# ASP_LEDBoard.net
KiCad netlist of a schematic drawn in Altium Designer
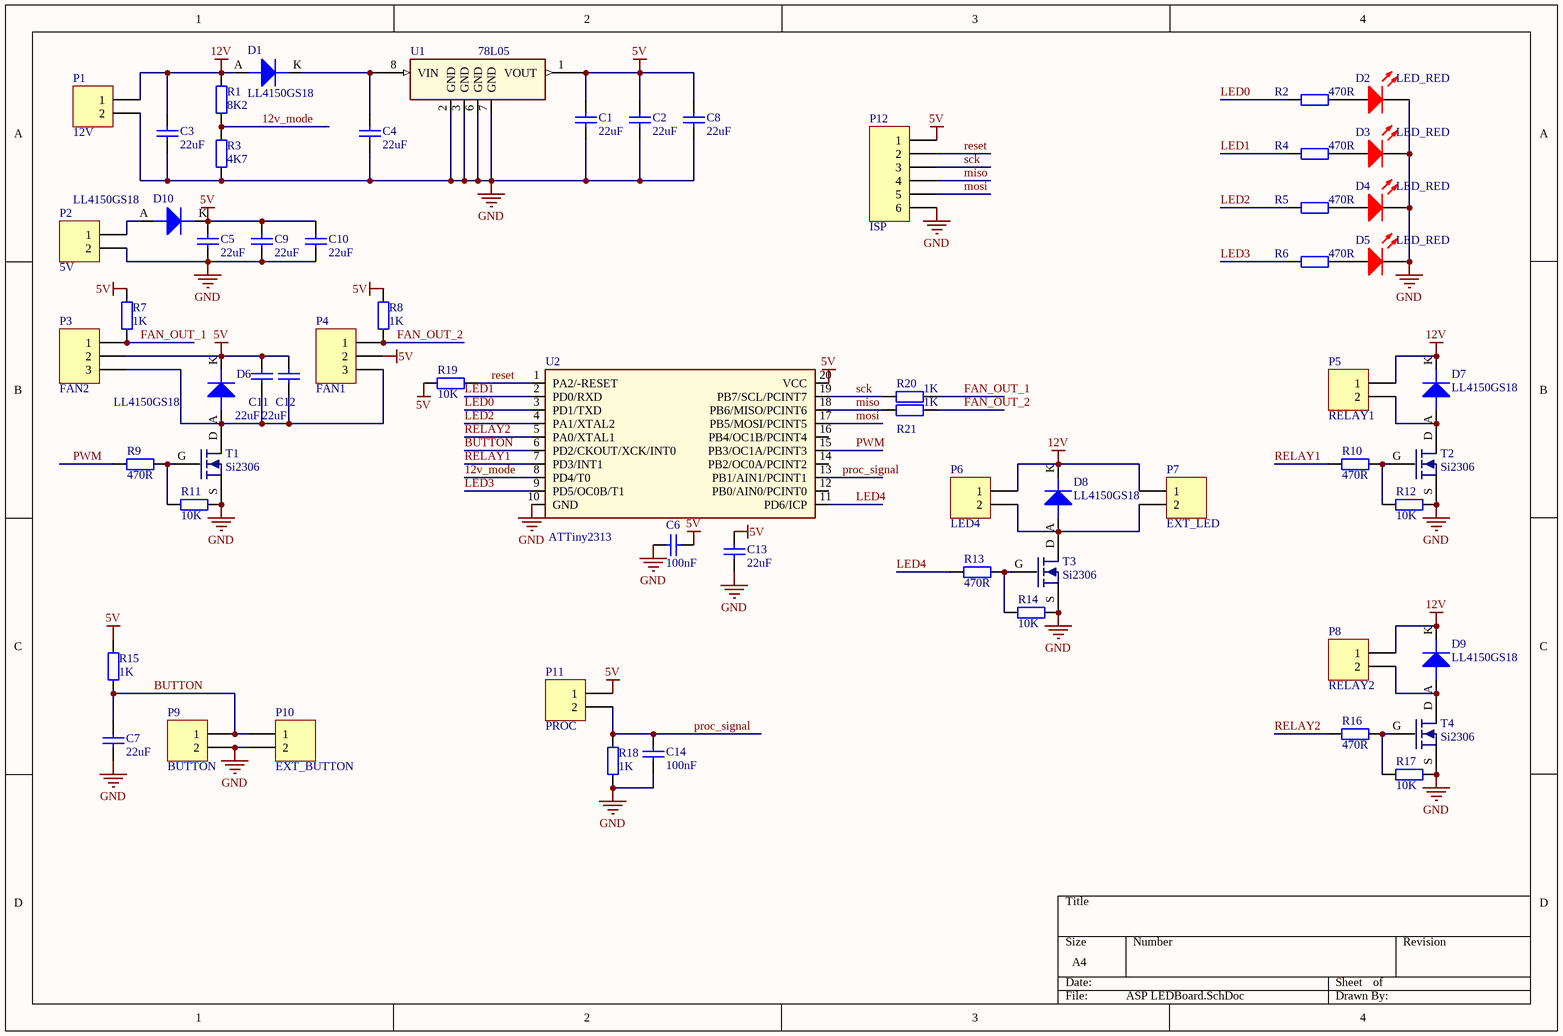
[diagram p0: ASP LEDBoard.SchDoc]

(export (version "E")
  (design (tool "Eeschema 10.0.6"))
  (components
    (comp (ref "C1")
      (value "22uF")
      (footprint "FP_0805_CAP_085")
      (description "Capacitor")
      (libsource (lib "Capacitor") (part "CAP"))
    )
    (comp (ref "C2")
      (value "22uF")
      (footprint "FP_0805_CAP_085")
      (description "Capacitor")
      (libsource (lib "Capacitor") (part "CAP"))
    )
    (comp (ref "C3")
      (value "22uF")
      (footprint "FP_0805_CAP_085")
      (description "Capacitor")
      (libsource (lib "Capacitor") (part "CAP"))
    )
    (comp (ref "C4")
      (value "22uF")
      (footprint "FP_0805_CAP_085")
      (description "Capacitor")
      (libsource (lib "Capacitor") (part "CAP"))
    )
    (comp (ref "C5")
      (value "22uF")
      (footprint "FP_0805_CAP_085")
      (description "Capacitor")
      (libsource (lib "Capacitor") (part "CAP"))
    )
    (comp (ref "C6")
      (value "100nF")
      (footprint "FP_0805_CAP_085")
      (description "Capacitor")
      (libsource (lib "Capacitor") (part "CAP"))
    )
    (comp (ref "C7")
      (value "22uF")
      (footprint "FP_0805_CAP_085")
      (description "Capacitor")
      (libsource (lib "Capacitor") (part "CAP"))
    )
    (comp (ref "C8")
      (value "22uF")
      (footprint "FP_0805_CAP_085")
      (description "Capacitor")
      (libsource (lib "Capacitor") (part "CAP"))
    )
    (comp (ref "C9")
      (value "22uF")
      (footprint "FP_0805_CAP_085")
      (description "Capacitor")
      (libsource (lib "Capacitor") (part "CAP"))
    )
    (comp (ref "C10")
      (value "22uF")
      (footprint "FP_0805_CAP_085")
      (description "Capacitor")
      (libsource (lib "Capacitor") (part "CAP"))
    )
    (comp (ref "C11")
      (value "22uF")
      (footprint "FP_0805_CAP_085")
      (description "Capacitor")
      (libsource (lib "Capacitor") (part "CAP"))
    )
    (comp (ref "C12")
      (value "22uF")
      (footprint "FP_0805_CAP_085")
      (description "Capacitor")
      (libsource (lib "Capacitor") (part "CAP"))
    )
    (comp (ref "C13")
      (value "22uF")
      (footprint "FP_0805_CAP_085")
      (description "Capacitor")
      (libsource (lib "Capacitor") (part "CAP"))
    )
    (comp (ref "C14")
      (value "100nF")
      (footprint "FP_0805_CAP_085")
      (description "Capacitor")
      (libsource (lib "Capacitor") (part "CAP"))
    )
    (comp (ref "D1") (value "LL4150GS18") (footprint "SOD-80") (libsource (lib "Diode") (part "DIODE_big")))
    (comp (ref "D2")
      (value "LED_RED")
      (footprint "1206 LED Reversed")
      (description "Typical LED")
      (libsource (lib "Led_optical") (part "LED_R"))
    )
    (comp (ref "D3")
      (value "LED_RED")
      (footprint "1206 LED Reversed")
      (description "Typical LED")
      (libsource (lib "Led_optical") (part "LED_R"))
    )
    (comp (ref "D4")
      (value "LED_RED")
      (footprint "1206 LED Reversed")
      (description "Typical LED")
      (libsource (lib "Led_optical") (part "LED_R"))
    )
    (comp (ref "D5")
      (value "LED_RED")
      (footprint "1206 LED Reversed")
      (description "Typical LED")
      (libsource (lib "Led_optical") (part "LED_R"))
    )
    (comp (ref "D6") (value "LL4150GS18") (footprint "SOD-80") (libsource (lib "Diode") (part "DIODE_big")))
    (comp (ref "D7") (value "LL4150GS18") (footprint "SOD-80") (libsource (lib "Diode") (part "DIODE_big")))
    (comp (ref "D8") (value "LL4150GS18") (footprint "SOD-80") (libsource (lib "Diode") (part "DIODE_big")))
    (comp (ref "D9") (value "LL4150GS18") (footprint "SOD-80") (libsource (lib "Diode") (part "DIODE_big")))
    (comp (ref "D10") (value "LL4150GS18") (footprint "SOD-80") (libsource (lib "Diode") (part "DIODE_big")))
    (comp (ref "P1")
      (value "12V")
      (footprint "HDR1X2")
      (description "Header, 2-Pin")
      (fields (field (name "PUBLISHER") "Altium Limited"))
      (libsource (lib "Miscellaneous Connectors") (part "Header 2"))
    )
    (comp (ref "P2")
      (value "5V")
      (footprint "HDR1X2")
      (description "Header, 2-Pin")
      (fields (field (name "PUBLISHER") "Altium Limited"))
      (libsource (lib "Miscellaneous Connectors") (part "Header 2"))
    )
    (comp (ref "P3")
      (value "FAN2")
      (footprint "HDR1X3")
      (description "Header, 3-Pin")
      (fields (field (name "PUBLISHER") "Altium Limited"))
      (libsource (lib "Miscellaneous Connectors") (part "Header 3"))
    )
    (comp (ref "P4")
      (value "FAN1")
      (footprint "HDR1X3")
      (description "Header, 3-Pin")
      (fields (field (name "PUBLISHER") "Altium Limited"))
      (libsource (lib "Miscellaneous Connectors") (part "Header 3"))
    )
    (comp (ref "P5")
      (value "RELAY1")
      (footprint "HDR1X2")
      (description "Header, 2-Pin")
      (fields (field (name "PUBLISHER") "Altium Limited"))
      (libsource (lib "Miscellaneous Connectors") (part "Header 2"))
    )
    (comp (ref "P6")
      (value "LED4")
      (footprint "HDR1X2")
      (description "Header, 2-Pin")
      (fields (field (name "PUBLISHER") "Altium Limited"))
      (libsource (lib "Miscellaneous Connectors") (part "Header 2"))
    )
    (comp (ref "P7")
      (value "EXT_LED")
      (footprint "HDR1X2")
      (description "Header, 2-Pin")
      (fields (field (name "PUBLISHER") "Altium Limited"))
      (libsource (lib "") (part "Header 2_1"))
    )
    (comp (ref "P8")
      (value "RELAY2")
      (footprint "HDR1X2")
      (description "Header, 2-Pin")
      (fields (field (name "PUBLISHER") "Altium Limited"))
      (libsource (lib "Miscellaneous Connectors") (part "Header 2"))
    )
    (comp (ref "P9")
      (value "BUTTON")
      (footprint "HDR1X2")
      (description "Header, 2-Pin")
      (fields (field (name "PUBLISHER") "Altium Limited"))
      (libsource (lib "Miscellaneous Connectors") (part "Header 2"))
    )
    (comp (ref "P10")
      (value "EXT_BUTTON")
      (footprint "HDR1X2")
      (description "Header, 2-Pin")
      (fields (field (name "PUBLISHER") "Altium Limited"))
      (libsource (lib "") (part "Header 2_1"))
    )
    (comp (ref "P11")
      (value "PROC")
      (footprint "HDR1X2")
      (description "Header, 2-Pin")
      (fields (field (name "PUBLISHER") "Altium Limited"))
      (libsource (lib "Miscellaneous Connectors") (part "Header 2"))
    )
    (comp (ref "P12")
      (value "ISP")
      (footprint "HDR1X6")
      (description "Header, 6-Pin")
      (fields (field (name "PUBLISHER") "Altium Limited"))
      (libsource (lib "Miscellaneous Connectors") (part "Header 6"))
    )
    (comp (ref "R1")
      (value "8K2")
      (footprint "FP_0805_RES")
      (description "Resistor")
      (libsource (lib "Resistor") (part "RES"))
    )
    (comp (ref "R2")
      (value "470R")
      (footprint "FP_0805_RES")
      (description "Resistor")
      (libsource (lib "") (part "RES_1"))
    )
    (comp (ref "R3")
      (value "4K7")
      (footprint "FP_0805_RES")
      (description "Resistor")
      (libsource (lib "") (part "RES_2"))
    )
    (comp (ref "R4")
      (value "470R")
      (footprint "FP_0805_RES")
      (description "Resistor")
      (libsource (lib "") (part "RES_1"))
    )
    (comp (ref "R5")
      (value "470R")
      (footprint "FP_0805_RES")
      (description "Resistor")
      (libsource (lib "") (part "RES_1"))
    )
    (comp (ref "R6")
      (value "470R")
      (footprint "FP_0805_RES")
      (description "Resistor")
      (libsource (lib "") (part "RES_1"))
    )
    (comp (ref "R7")
      (value "1K")
      (footprint "FP_0805_RES")
      (description "Resistor")
      (libsource (lib "Resistor") (part "RES"))
    )
    (comp (ref "R8")
      (value "1K")
      (footprint "FP_0805_RES")
      (description "Resistor")
      (libsource (lib "Resistor") (part "RES"))
    )
    (comp (ref "R9")
      (value "470R")
      (footprint "FP_0805_RES")
      (description "Resistor")
      (libsource (lib "") (part "RES_1"))
    )
    (comp (ref "R10")
      (value "470R")
      (footprint "FP_0805_RES")
      (description "Resistor")
      (libsource (lib "") (part "RES_1"))
    )
    (comp (ref "R11")
      (value "10K")
      (footprint "FP_0805_RES")
      (description "Resistor")
      (libsource (lib "") (part "RES_1"))
    )
    (comp (ref "R12")
      (value "10K")
      (footprint "FP_0805_RES")
      (description "Resistor")
      (libsource (lib "") (part "RES_1"))
    )
    (comp (ref "R13")
      (value "470R")
      (footprint "FP_0805_RES")
      (description "Resistor")
      (libsource (lib "") (part "RES_1"))
    )
    (comp (ref "R14")
      (value "10K")
      (footprint "FP_0805_RES")
      (description "Resistor")
      (libsource (lib "") (part "RES_1"))
    )
    (comp (ref "R15")
      (value "1K")
      (footprint "FP_0805_RES")
      (description "Resistor")
      (libsource (lib "Resistor") (part "RES"))
    )
    (comp (ref "R16")
      (value "470R")
      (footprint "FP_0805_RES")
      (description "Resistor")
      (libsource (lib "") (part "RES_1"))
    )
    (comp (ref "R17")
      (value "10K")
      (footprint "FP_0805_RES")
      (description "Resistor")
      (libsource (lib "") (part "RES_1"))
    )
    (comp (ref "R18")
      (value "1K")
      (footprint "FP_0805_RES")
      (description "Resistor")
      (libsource (lib "") (part "RES_2"))
    )
    (comp (ref "R19")
      (value "10K")
      (footprint "FP_0805_RES")
      (description "Resistor")
      (libsource (lib "") (part "RES_1"))
    )
    (comp (ref "R20")
      (value "1K")
      (footprint "FP_0805_RES")
      (description "Resistor")
      (libsource (lib "") (part "RES_1"))
    )
    (comp (ref "R21")
      (value "1K")
      (footprint "FP_0805_RES")
      (description "Resistor")
      (libsource (lib "") (part "RES_1"))
    )
    (comp (ref "T1") (value "Si2306") (footprint "FET_SOT23") (libsource (lib "FET") (part "NMOS")))
    (comp (ref "T2") (value "Si2306") (footprint "FET_SOT23") (libsource (lib "FET") (part "NMOS")))
    (comp (ref "T3") (value "Si2306") (footprint "FET_SOT23") (libsource (lib "FET") (part "NMOS")))
    (comp (ref "T4") (value "Si2306") (footprint "FET_SOT23") (libsource (lib "FET") (part "NMOS")))
    (comp (ref "U1")
      (value "78L05")
      (footprint "Supply_SOIC8")
      (libsource (lib "Supply") (part "78Lxx_SOIC"))
    )
    (comp (ref "U2")
      (value "ATTiny2313")
      (footprint "DIGITAL_SOIC20W")
      (libsource (lib "uC") (part "ATTiny2313"))
    )
  )
  (nets
    (net (code "1") (name "/12v_mode") (class "Default")
      (node (ref "R1") (pin "1") (pinfunction "1_1") (pintype "passive"))
      (node (ref "R3") (pin "1") (pinfunction "1_1") (pintype "passive"))
      (node (ref "U2") (pin "8") (pinfunction "PD4/T0_8") (pintype "passive"))
    )
    (net (code "2") (name "/BUTTON") (class "Default")
      (node (ref "C7") (pin "2") (pinfunction "2_2") (pintype "passive"))
      (node (ref "P10") (pin "1") (pinfunction "1_1") (pintype "passive"))
      (node (ref "P9") (pin "1") (pinfunction "1_1") (pintype "passive"))
      (node (ref "R15") (pin "1") (pinfunction "1_1") (pintype "passive"))
      (node (ref "U2") (pin "6") (pinfunction "PD2/CKOUT/XCK/INT0_6") (pintype "passive"))
    )
    (net (code "3") (name "/FAN_OUT_1") (class "Default")
      (node (ref "P3") (pin "1") (pinfunction "1_1") (pintype "passive"))
      (node (ref "R20") (pin "1") (pinfunction "1_1") (pintype "passive"))
      (node (ref "R7") (pin "1") (pinfunction "1_1") (pintype "passive"))
    )
    (net (code "4") (name "/FAN_OUT_2") (class "Default")
      (node (ref "P4") (pin "1") (pinfunction "1_1") (pintype "passive"))
      (node (ref "R21") (pin "1") (pinfunction "1_1") (pintype "passive"))
      (node (ref "R8") (pin "1") (pinfunction "1_1") (pintype "passive"))
    )
    (net (code "5") (name "/LED0") (class "Default")
      (node (ref "R2") (pin "2") (pinfunction "2_2") (pintype "passive"))
      (node (ref "U2") (pin "3") (pinfunction "PD1/TXD_3") (pintype "passive"))
    )
    (net (code "6") (name "/LED1") (class "Default")
      (node (ref "R4") (pin "2") (pinfunction "2_2") (pintype "passive"))
      (node (ref "U2") (pin "2") (pinfunction "PD0/RXD_2") (pintype "passive"))
    )
    (net (code "7") (name "/LED2") (class "Default")
      (node (ref "R5") (pin "2") (pinfunction "2_2") (pintype "passive"))
      (node (ref "U2") (pin "4") (pinfunction "PA1/XTAL2_4") (pintype "passive"))
    )
    (net (code "8") (name "/LED3") (class "Default")
      (node (ref "R6") (pin "2") (pinfunction "2_2") (pintype "passive"))
      (node (ref "U2") (pin "9") (pinfunction "PD5/OC0B/T1_9") (pintype "passive"))
    )
    (net (code "9") (name "/LED4") (class "Default")
      (node (ref "R13") (pin "2") (pinfunction "2_2") (pintype "passive"))
      (node (ref "U2") (pin "11") (pinfunction "PD6/ICP_11") (pintype "passive"))
    )
    (net (code "10") (name "/PWM") (class "Default")
      (node (ref "R9") (pin "2") (pinfunction "2_2") (pintype "passive"))
      (node (ref "U2") (pin "15") (pinfunction "PB3/OC1A/PCINT3_15") (pintype "passive"))
    )
    (net (code "11") (name "/RELAY1") (class "Default")
      (node (ref "R10") (pin "2") (pinfunction "2_2") (pintype "passive"))
      (node (ref "U2") (pin "7") (pinfunction "PD3/INT1_7") (pintype "passive"))
    )
    (net (code "12") (name "/RELAY2") (class "Default")
      (node (ref "R16") (pin "2") (pinfunction "2_2") (pintype "passive"))
      (node (ref "U2") (pin "5") (pinfunction "PA0/XTAL1_5") (pintype "passive"))
    )
    (net (code "13") (name "/miso") (class "Default")
      (node (ref "P12") (pin "4") (pinfunction "4_4") (pintype "passive"))
      (node (ref "R21") (pin "2") (pinfunction "2_2") (pintype "passive"))
      (node (ref "U2") (pin "18") (pinfunction "PB6/MISO/PCINT6_18") (pintype "passive"))
    )
    (net (code "14") (name "/mosi") (class "Default")
      (node (ref "P12") (pin "5") (pinfunction "5_5") (pintype "passive"))
      (node (ref "U2") (pin "17") (pinfunction "PB5/MOSI/PCINT5_17") (pintype "passive"))
    )
    (net (code "15") (name "/proc_signal") (class "Default")
      (node (ref "C14") (pin "2") (pinfunction "2_2") (pintype "passive"))
      (node (ref "P11") (pin "2") (pinfunction "2_2") (pintype "passive"))
      (node (ref "R18") (pin "1") (pinfunction "1_1") (pintype "passive"))
      (node (ref "U2") (pin "13") (pinfunction "PB1/AIN1/PCINT1_13") (pintype "passive"))
    )
    (net (code "16") (name "/reset") (class "Default")
      (node (ref "P12") (pin "2") (pinfunction "2_2") (pintype "passive"))
      (node (ref "R19") (pin "1") (pinfunction "1_1") (pintype "passive"))
      (node (ref "U2") (pin "1") (pinfunction "PA2/-RESET_1") (pintype "passive"))
    )
    (net (code "17") (name "/sck") (class "Default")
      (node (ref "P12") (pin "3") (pinfunction "3_3") (pintype "passive"))
      (node (ref "R20") (pin "2") (pinfunction "2_2") (pintype "passive"))
      (node (ref "U2") (pin "19") (pinfunction "PB7/SCL/PCINT7_19") (pintype "passive"))
    )
    (net (code "18") (name "5V") (class "Default")
      (node (ref "C1") (pin "2") (pinfunction "2_2") (pintype "passive"))
      (node (ref "C10") (pin "2") (pinfunction "2_2") (pintype "passive"))
      (node (ref "C11") (pin "2") (pinfunction "2_2") (pintype "passive"))
      (node (ref "C12") (pin "2") (pinfunction "2_2") (pintype "passive"))
      (node (ref "C13") (pin "2") (pinfunction "2_2") (pintype "passive"))
      (node (ref "C2") (pin "2") (pinfunction "2_2") (pintype "passive"))
      (node (ref "C5") (pin "2") (pinfunction "2_2") (pintype "passive"))
      (node (ref "C6") (pin "2") (pinfunction "2_2") (pintype "passive"))
      (node (ref "C8") (pin "2") (pinfunction "2_2") (pintype "passive"))
      (node (ref "C9") (pin "2") (pinfunction "2_2") (pintype "passive"))
      (node (ref "D10") (pin "K") (pinfunction "K_K") (pintype "passive"))
      (node (ref "D6") (pin "K") (pinfunction "K_K") (pintype "passive"))
      (node (ref "P11") (pin "1") (pinfunction "1_1") (pintype "passive"))
      (node (ref "P12") (pin "1") (pinfunction "1_1") (pintype "passive"))
      (node (ref "P3") (pin "2") (pinfunction "2_2") (pintype "passive"))
      (node (ref "P4") (pin "2") (pinfunction "2_2") (pintype "passive"))
      (node (ref "R15") (pin "2") (pinfunction "2_2") (pintype "passive"))
      (node (ref "R19") (pin "2") (pinfunction "2_2") (pintype "passive"))
      (node (ref "R7") (pin "2") (pinfunction "2_2") (pintype "passive"))
      (node (ref "R8") (pin "2") (pinfunction "2_2") (pintype "passive"))
      (node (ref "U1") (pin "1") (pinfunction "VOUT_1") (pintype "output"))
      (node (ref "U2") (pin "20") (pinfunction "VCC_20") (pintype "passive"))
    )
    (net (code "19") (name "12V") (class "Default")
      (node (ref "C3") (pin "2") (pinfunction "2_2") (pintype "passive"))
      (node (ref "D1") (pin "A") (pinfunction "A_A") (pintype "passive"))
      (node (ref "D7") (pin "K") (pinfunction "K_K") (pintype "passive"))
      (node (ref "D8") (pin "K") (pinfunction "K_K") (pintype "passive"))
      (node (ref "D9") (pin "K") (pinfunction "K_K") (pintype "passive"))
      (node (ref "P1") (pin "1") (pinfunction "1_1") (pintype "passive"))
      (node (ref "P5") (pin "1") (pinfunction "1_1") (pintype "passive"))
      (node (ref "P6") (pin "1") (pinfunction "1_1") (pintype "passive"))
      (node (ref "P7") (pin "1") (pinfunction "1_1") (pintype "passive"))
      (node (ref "P8") (pin "1") (pinfunction "1_1") (pintype "passive"))
      (node (ref "R1") (pin "2") (pinfunction "2_2") (pintype "passive"))
    )
    (net (code "20") (name "GND") (class "Default")
      (node (ref "C1") (pin "1") (pinfunction "1_1") (pintype "passive"))
      (node (ref "C10") (pin "1") (pinfunction "1_1") (pintype "passive"))
      (node (ref "C13") (pin "1") (pinfunction "1_1") (pintype "passive"))
      (node (ref "C14") (pin "1") (pinfunction "1_1") (pintype "passive"))
      (node (ref "C2") (pin "1") (pinfunction "1_1") (pintype "passive"))
      (node (ref "C3") (pin "1") (pinfunction "1_1") (pintype "passive"))
      (node (ref "C4") (pin "1") (pinfunction "1_1") (pintype "passive"))
      (node (ref "C5") (pin "1") (pinfunction "1_1") (pintype "passive"))
      (node (ref "C6") (pin "1") (pinfunction "1_1") (pintype "passive"))
      (node (ref "C7") (pin "1") (pinfunction "1_1") (pintype "passive"))
      (node (ref "C8") (pin "1") (pinfunction "1_1") (pintype "passive"))
      (node (ref "C9") (pin "1") (pinfunction "1_1") (pintype "passive"))
      (node (ref "D2") (pin "K") (pinfunction "K_K") (pintype "passive"))
      (node (ref "D3") (pin "K") (pinfunction "K_K") (pintype "passive"))
      (node (ref "D4") (pin "K") (pinfunction "K_K") (pintype "passive"))
      (node (ref "D5") (pin "K") (pinfunction "K_K") (pintype "passive"))
      (node (ref "P1") (pin "2") (pinfunction "2_2") (pintype "passive"))
      (node (ref "P10") (pin "2") (pinfunction "2_2") (pintype "passive"))
      (node (ref "P12") (pin "6") (pinfunction "6_6") (pintype "passive"))
      (node (ref "P2") (pin "2") (pinfunction "2_2") (pintype "passive"))
      (node (ref "P9") (pin "2") (pinfunction "2_2") (pintype "passive"))
      (node (ref "R11") (pin "1") (pinfunction "1_1") (pintype "passive"))
      (node (ref "R12") (pin "1") (pinfunction "1_1") (pintype "passive"))
      (node (ref "R14") (pin "1") (pinfunction "1_1") (pintype "passive"))
      (node (ref "R17") (pin "1") (pinfunction "1_1") (pintype "passive"))
      (node (ref "R18") (pin "2") (pinfunction "2_2") (pintype "passive"))
      (node (ref "R3") (pin "2") (pinfunction "2_2") (pintype "passive"))
      (node (ref "T1") (pin "S") (pinfunction "S_S") (pintype "passive"))
      (node (ref "T2") (pin "S") (pinfunction "S_S") (pintype "passive"))
      (node (ref "T3") (pin "S") (pinfunction "S_S") (pintype "passive"))
      (node (ref "T4") (pin "S") (pinfunction "S_S") (pintype "passive"))
      (node (ref "U1") (pin "2") (pinfunction "GND_2") (pintype "power_in"))
      (node (ref "U1") (pin "3") (pinfunction "GND_3") (pintype "power_in"))
      (node (ref "U1") (pin "6") (pinfunction "GND_6") (pintype "power_in"))
      (node (ref "U1") (pin "7") (pinfunction "GND_7") (pintype "power_in"))
      (node (ref "U2") (pin "10") (pinfunction "GND_10") (pintype "passive"))
    )
    (net (code "21") (name "Net-(C11-Pad1)") (class "Default")
      (node (ref "C11") (pin "1") (pinfunction "1_1") (pintype "passive"))
      (node (ref "C12") (pin "1") (pinfunction "1_1") (pintype "passive"))
      (node (ref "D6") (pin "A") (pinfunction "A_A") (pintype "passive"))
      (node (ref "P3") (pin "3") (pinfunction "3_3") (pintype "passive"))
      (node (ref "P4") (pin "3") (pinfunction "3_3") (pintype "passive"))
      (node (ref "T1") (pin "D") (pinfunction "D_D") (pintype "passive"))
    )
    (net (code "22") (name "Net-(D2-PadA)") (class "Default")
      (node (ref "D2") (pin "A") (pinfunction "A_A") (pintype "passive"))
      (node (ref "R2") (pin "1") (pinfunction "1_1") (pintype "passive"))
    )
    (net (code "23") (name "Net-(D3-PadA)") (class "Default")
      (node (ref "D3") (pin "A") (pinfunction "A_A") (pintype "passive"))
      (node (ref "R4") (pin "1") (pinfunction "1_1") (pintype "passive"))
    )
    (net (code "24") (name "Net-(D4-PadA)") (class "Default")
      (node (ref "D4") (pin "A") (pinfunction "A_A") (pintype "passive"))
      (node (ref "R5") (pin "1") (pinfunction "1_1") (pintype "passive"))
    )
    (net (code "25") (name "Net-(D5-PadA)") (class "Default")
      (node (ref "D5") (pin "A") (pinfunction "A_A") (pintype "passive"))
      (node (ref "R6") (pin "1") (pinfunction "1_1") (pintype "passive"))
    )
    (net (code "26") (name "Net-(D7-PadA)") (class "Default")
      (node (ref "D7") (pin "A") (pinfunction "A_A") (pintype "passive"))
      (node (ref "P5") (pin "2") (pinfunction "2_2") (pintype "passive"))
      (node (ref "T2") (pin "D") (pinfunction "D_D") (pintype "passive"))
    )
    (net (code "27") (name "Net-(D8-PadA)") (class "Default")
      (node (ref "D8") (pin "A") (pinfunction "A_A") (pintype "passive"))
      (node (ref "P6") (pin "2") (pinfunction "2_2") (pintype "passive"))
      (node (ref "P7") (pin "2") (pinfunction "2_2") (pintype "passive"))
      (node (ref "T3") (pin "D") (pinfunction "D_D") (pintype "passive"))
    )
    (net (code "28") (name "Net-(D9-PadA)") (class "Default")
      (node (ref "D9") (pin "A") (pinfunction "A_A") (pintype "passive"))
      (node (ref "P8") (pin "2") (pinfunction "2_2") (pintype "passive"))
      (node (ref "T4") (pin "D") (pinfunction "D_D") (pintype "passive"))
    )
    (net (code "29") (name "Net-(D10-PadA)") (class "Default")
      (node (ref "D10") (pin "A") (pinfunction "A_A") (pintype "passive"))
      (node (ref "P2") (pin "1") (pinfunction "1_1") (pintype "passive"))
    )
    (net (code "30") (name "Net-(R10-Pad1)") (class "Default")
      (node (ref "R10") (pin "1") (pinfunction "1_1") (pintype "passive"))
      (node (ref "R12") (pin "2") (pinfunction "2_2") (pintype "passive"))
      (node (ref "T2") (pin "G") (pinfunction "G_G") (pintype "passive"))
    )
    (net (code "31") (name "Net-(R11-Pad2)") (class "Default")
      (node (ref "R11") (pin "2") (pinfunction "2_2") (pintype "passive"))
      (node (ref "R9") (pin "1") (pinfunction "1_1") (pintype "passive"))
      (node (ref "T1") (pin "G") (pinfunction "G_G") (pintype "passive"))
    )
    (net (code "32") (name "Net-(R13-Pad1)") (class "Default")
      (node (ref "R13") (pin "1") (pinfunction "1_1") (pintype "passive"))
      (node (ref "R14") (pin "2") (pinfunction "2_2") (pintype "passive"))
      (node (ref "T3") (pin "G") (pinfunction "G_G") (pintype "passive"))
    )
    (net (code "33") (name "Net-(R16-Pad1)") (class "Default")
      (node (ref "R16") (pin "1") (pinfunction "1_1") (pintype "passive"))
      (node (ref "R17") (pin "2") (pinfunction "2_2") (pintype "passive"))
      (node (ref "T4") (pin "G") (pinfunction "G_G") (pintype "passive"))
    )
    (net (code "34") (name "Net-(U1-VIN)") (class "Default")
      (node (ref "C4") (pin "2") (pinfunction "2_2") (pintype "passive"))
      (node (ref "D1") (pin "K") (pinfunction "K_K") (pintype "passive"))
      (node (ref "U1") (pin "8") (pinfunction "VIN_8") (pintype "input"))
    )
    (net (code "35") (name "unconnected-(U2-PB0{slash}AIN0{slash}PCINT0-Pad12)") (class "Default")
      (node (ref "U2") (pin "12") (pinfunction "PB0/AIN0/PCINT0_12") (pintype "passive"))
    )
    (net (code "36") (name "unconnected-(U2-PB2{slash}OC0A{slash}PCINT2-Pad14)") (class "Default")
      (node (ref "U2") (pin "14") (pinfunction "PB2/OC0A/PCINT2_14") (pintype "passive"))
    )
    (net (code "37") (name "unconnected-(U2-PB4{slash}OC1B{slash}PCINT4-Pad16)") (class "Default")
      (node (ref "U2") (pin "16") (pinfunction "PB4/OC1B/PCINT4_16") (pintype "passive"))
    )
  )
)
